# hydrogen_sensors_board_v2.net
KiCad netlist of a schematic drawn in EAGLE
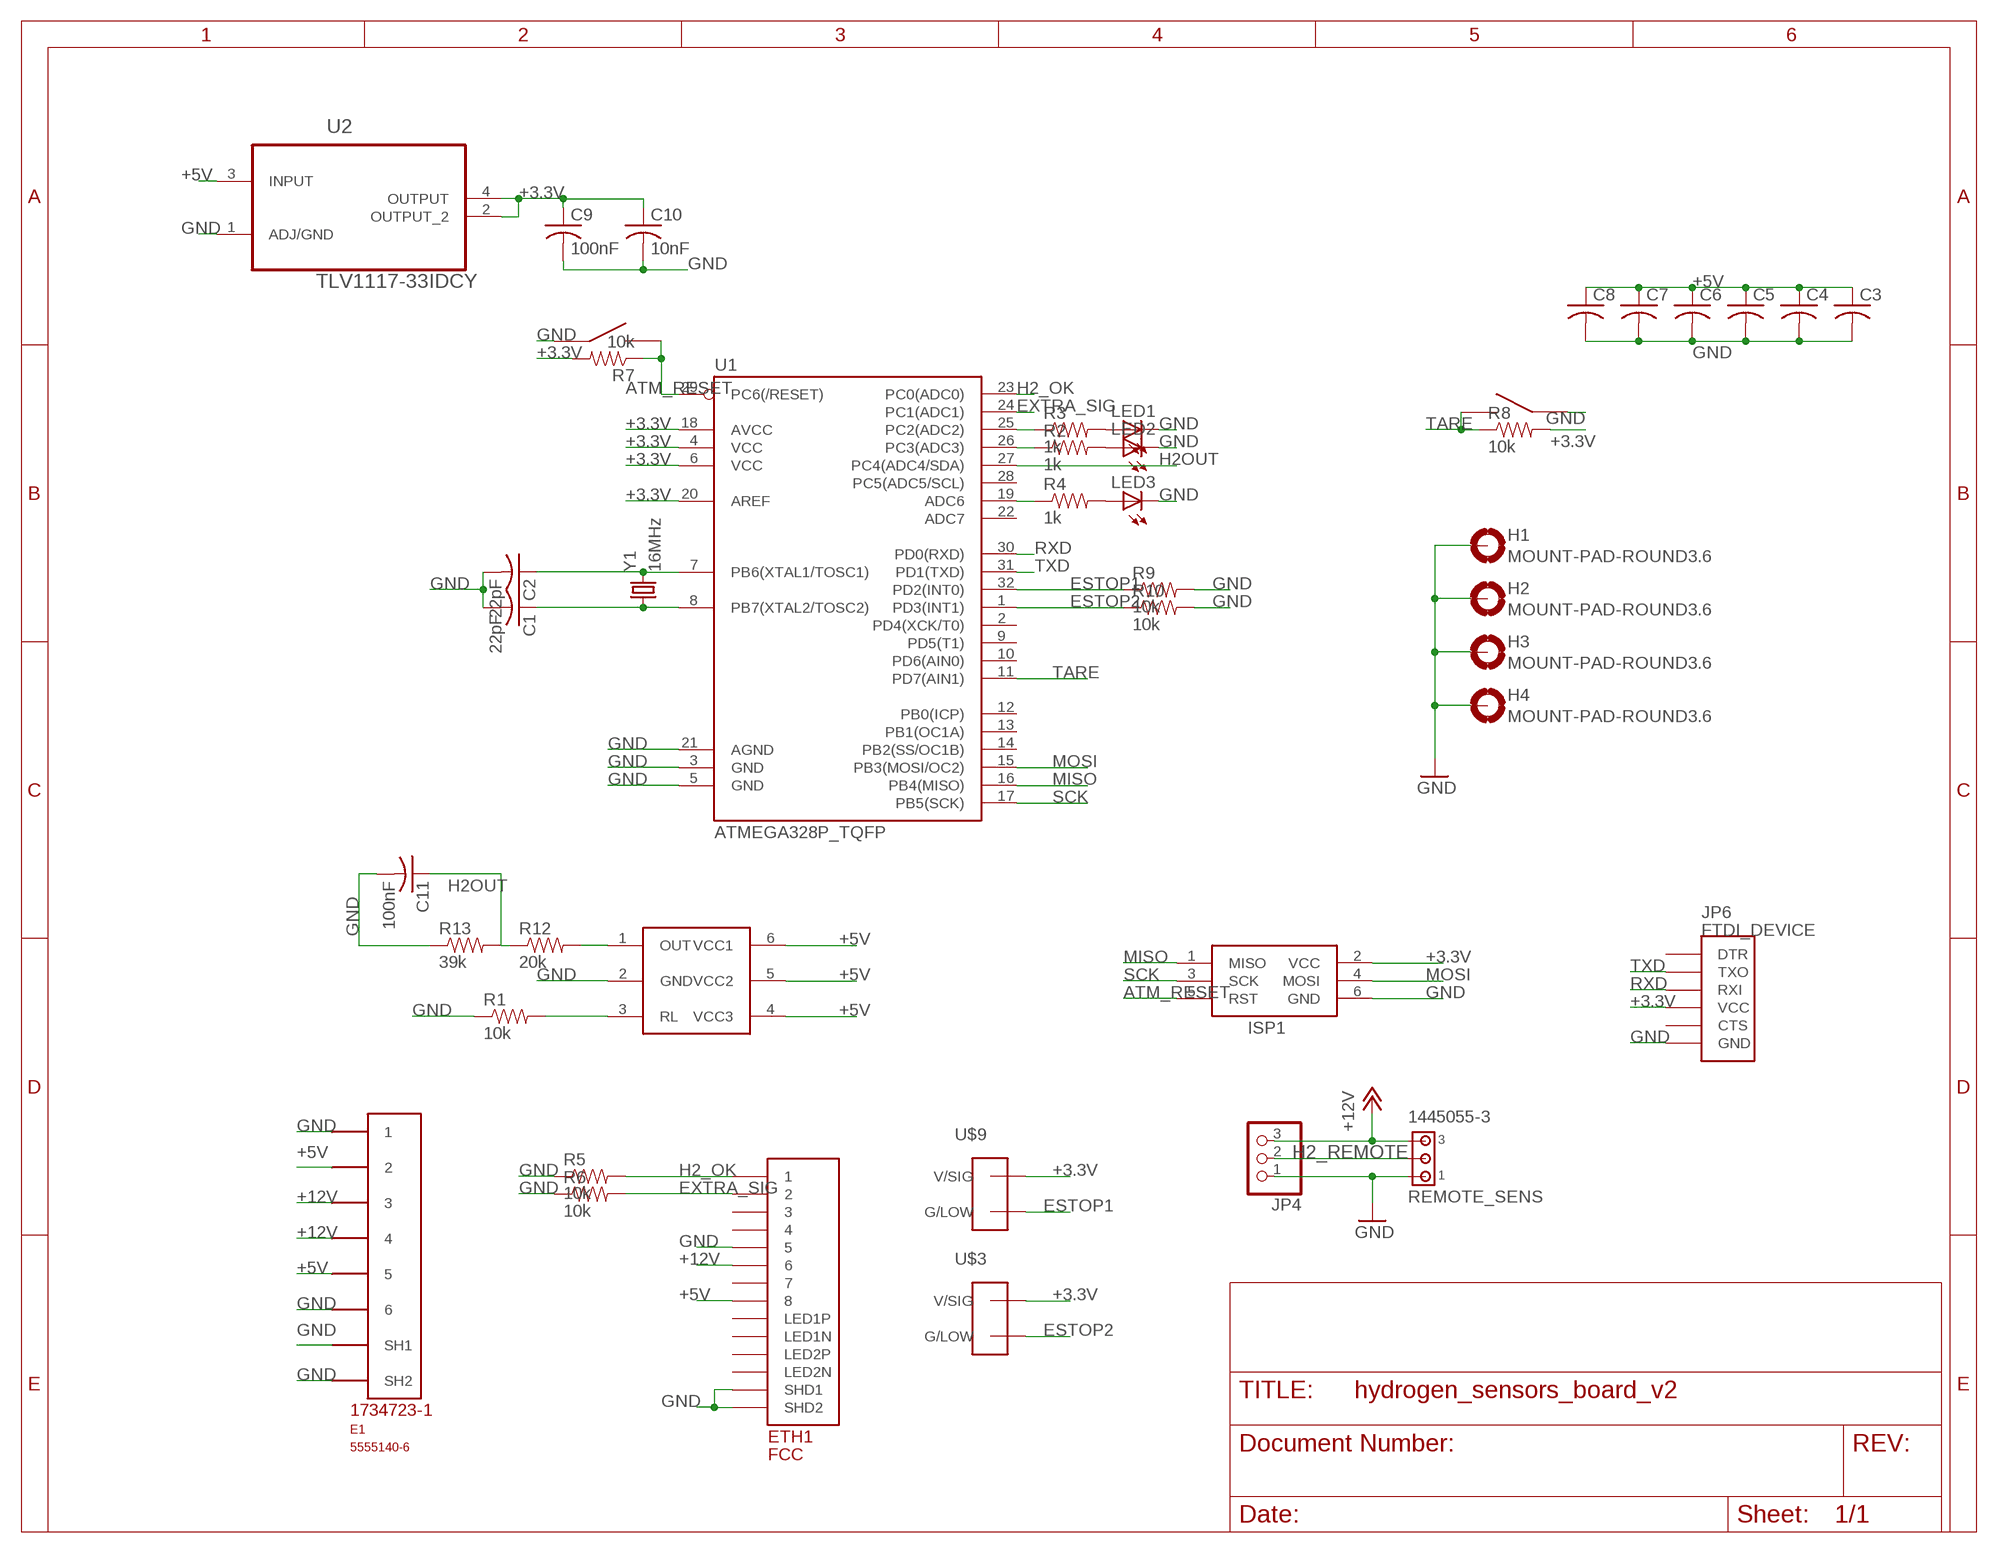
[diagram p0: schematic, sheet 1]

(export (version "E")
  (design (tool "Eeschema 10.0.6"))
  (components
    (comp (ref "C1")
      (value "22pF")
      (footprint "eagle-import:C0603K")
      (libsource (lib "eagle-import") (part "C-USC0603K"))
    )
    (comp (ref "C2")
      (value "22pF")
      (footprint "eagle-import:C0603K")
      (libsource (lib "eagle-import") (part "C-USC0603K"))
    )
    (comp (ref "C3")
      (value "C-USC0603")
      (footprint "eagle-import:C0603")
      (libsource (lib "eagle-import") (part "C-USC0603"))
    )
    (comp (ref "C4")
      (value "C-USC0603")
      (footprint "eagle-import:C0603")
      (libsource (lib "eagle-import") (part "C-USC0603"))
    )
    (comp (ref "C5")
      (value "C-USC0603")
      (footprint "eagle-import:C0603")
      (libsource (lib "eagle-import") (part "C-USC0603"))
    )
    (comp (ref "C6")
      (value "C-USC0603")
      (footprint "eagle-import:C0603")
      (libsource (lib "eagle-import") (part "C-USC0603"))
    )
    (comp (ref "C7")
      (value "C-USC0603")
      (footprint "eagle-import:C0603")
      (libsource (lib "eagle-import") (part "C-USC0603"))
    )
    (comp (ref "C8")
      (value "C-USC0603")
      (footprint "eagle-import:C0603")
      (libsource (lib "eagle-import") (part "C-USC0603"))
    )
    (comp (ref "C9")
      (value "100nF")
      (footprint "eagle-import:C0603")
      (libsource (lib "eagle-import") (part "C-USC0603"))
    )
    (comp (ref "C10")
      (value "10nF")
      (footprint "eagle-import:C0603")
      (libsource (lib "eagle-import") (part "C-USC0603"))
    )
    (comp (ref "C11")
      (value "100nF")
      (footprint "eagle-import:C0603")
      (libsource (lib "eagle-import") (part "C-USC0603"))
    )
    (comp (ref "E1")
      (value "5555140-6")
      (footprint "eagle-import:1734723-1_RJ11")
      (libsource (lib "eagle-import") (part "5555140-6"))
    )
    (comp (ref "ETH1")
      (value "FCC")
      (footprint "eagle-import:A122645-ND")
      (libsource (lib "eagle-import") (part "ETHERNET"))
    )
    (comp (ref "H1")
      (value "MOUNT-PAD-ROUND3.6")
      (footprint "eagle-import:3,6-PAD")
      (libsource (lib "eagle-import") (part "MOUNT-PAD-ROUND3.6"))
    )
    (comp (ref "H2")
      (value "MOUNT-PAD-ROUND3.6")
      (footprint "eagle-import:3,6-PAD")
      (libsource (lib "eagle-import") (part "MOUNT-PAD-ROUND3.6"))
    )
    (comp (ref "H3")
      (value "MOUNT-PAD-ROUND3.6")
      (footprint "eagle-import:3,6-PAD")
      (libsource (lib "eagle-import") (part "MOUNT-PAD-ROUND3.6"))
    )
    (comp (ref "H4")
      (value "MOUNT-PAD-ROUND3.6")
      (footprint "eagle-import:3,6-PAD")
      (libsource (lib "eagle-import") (part "MOUNT-PAD-ROUND3.6"))
    )
    (comp (ref "ISP1")
      (value "AVRISP-BOX")
      (footprint "eagle-import:AVRISP-BOX")
      (libsource (lib "eagle-import") (part "AVRISP-BOX"))
    )
    (comp (ref "JP4")
      (value "PINHD-1X3")
      (footprint "eagle-import:1X03")
      (libsource (lib "eagle-import") (part "PINHD-1X3"))
    )
    (comp (ref "JP6")
      (value "FTDI_DEVICE")
      (footprint "eagle-import:FTDI_DEVICE_SIDE")
      (libsource (lib "eagle-import") (part "FTDI_DEVICE"))
    )
    (comp (ref "LED1")
      (value "LEDCHIPLED_0805")
      (footprint "eagle-import:CHIPLED_0805")
      (libsource (lib "eagle-import") (part "LEDCHIPLED_0805"))
    )
    (comp (ref "LED2")
      (value "LEDCHIPLED_0805")
      (footprint "eagle-import:CHIPLED_0805")
      (libsource (lib "eagle-import") (part "LEDCHIPLED_0805"))
    )
    (comp (ref "LED3")
      (value "LEDCHIPLED_0805")
      (footprint "eagle-import:CHIPLED_0805")
      (libsource (lib "eagle-import") (part "LEDCHIPLED_0805"))
    )
    (comp (ref "R1")
      (value "10k")
      (footprint "eagle-import:0603-RES")
      (libsource (lib "eagle-import") (part "RESISTOR0603-RES"))
    )
    (comp (ref "R2")
      (value "1k")
      (footprint "eagle-import:0603-RES")
      (libsource (lib "eagle-import") (part "SparkFun-Resistors_RESISTOR0603-RES"))
    )
    (comp (ref "R3")
      (value "1k")
      (footprint "eagle-import:0603-RES")
      (libsource (lib "eagle-import") (part "SparkFun-Resistors_RESISTOR0603-RES"))
    )
    (comp (ref "R4")
      (value "1k")
      (footprint "eagle-import:0603-RES")
      (libsource (lib "eagle-import") (part "SparkFun-Resistors_RESISTOR0603-RES"))
    )
    (comp (ref "R5")
      (value "10k")
      (footprint "eagle-import:0603-RES")
      (libsource (lib "eagle-import") (part "RESISTOR0603-RES"))
    )
    (comp (ref "R6")
      (value "10k")
      (footprint "eagle-import:0603-RES")
      (libsource (lib "eagle-import") (part "RESISTOR0603-RES"))
    )
    (comp (ref "R7")
      (value "10k")
      (footprint "eagle-import:0603-RES")
      (libsource (lib "eagle-import") (part "SparkFun-Resistors_RESISTOR0603-RES"))
    )
    (comp (ref "R8")
      (value "10k")
      (footprint "eagle-import:0603-RES")
      (libsource (lib "eagle-import") (part "SparkFun-Resistors_RESISTOR0603-RES"))
    )
    (comp (ref "R9")
      (value "10k")
      (footprint "eagle-import:0603-RES")
      (libsource (lib "eagle-import") (part "RESISTOR0603-RES"))
    )
    (comp (ref "R10")
      (value "10k")
      (footprint "eagle-import:0603-RES")
      (libsource (lib "eagle-import") (part "RESISTOR0603-RES"))
    )
    (comp (ref "R12")
      (value "20k")
      (footprint "eagle-import:0603-RES")
      (libsource (lib "eagle-import") (part "RESISTOR0603-RES"))
    )
    (comp (ref "R13")
      (value "39k")
      (footprint "eagle-import:0603-RES")
      (libsource (lib "eagle-import") (part "RESISTOR0603-RES"))
    )
    (comp (ref "REMOTE_SENS")
      (value "1445055-3")
      (footprint "eagle-import:1445055-3")
      (libsource (lib "eagle-import") (part "1445055-3"))
    )
    (comp (ref "U$1")
      (value "MQ-8MQ-8")
      (footprint "eagle-import:MQ-8")
      (libsource (lib "eagle-import") (part "MQ-8MQ-8"))
    )
    (comp (ref "U$2")
      (value "EG4621CT-ND")
      (footprint "eagle-import:EG4621CT-ND")
      (libsource (lib "eagle-import") (part "EG4621CT-ND"))
    )
    (comp (ref "U$3")
      (value "TE770966")
      (footprint "eagle-import:2X1-MATE-N-LOCK")
      (libsource (lib "eagle-import") (part "TE770966"))
    )
    (comp (ref "U$9")
      (value "TE770966")
      (footprint "eagle-import:2X1-MATE-N-LOCK")
      (libsource (lib "eagle-import") (part "TE770966"))
    )
    (comp (ref "U$10")
      (value "EG4621CT-ND")
      (footprint "eagle-import:EG4621CT-ND")
      (libsource (lib "eagle-import") (part "EG4621CT-ND"))
    )
    (comp (ref "U1")
      (value "ATMEGA328P_TQFP")
      (footprint "eagle-import:TQFP32-08")
      (libsource (lib "eagle-import") (part "ATMEGA328P_TQFP"))
    )
    (comp (ref "U2")
      (value "TLV1117-33IDCY")
      (footprint "eagle-import:SOT230P700X180-4N")
      (libsource (lib "eagle-import") (part "TLV1117-33IDCY"))
    )
    (comp (ref "Y1")
      (value "16MHz")
      (footprint "eagle-import:HC49US")
      (libsource (lib "eagle-import") (part "CRYSTALHC49US"))
    )
  )
  (nets
    (net (code "1") (name "+12V") (class "Default")
      (node (ref "E1") (pin "3") (pinfunction "3_3") (pintype "bidirectional"))
      (node (ref "E1") (pin "4") (pinfunction "4_4") (pintype "bidirectional"))
      (node (ref "ETH1") (pin "P$6") (pinfunction "6_P$6") (pintype "bidirectional"))
      (node (ref "JP4") (pin "3") (pinfunction "3_3") (pintype "passive"))
      (node (ref "REMOTE_SENS") (pin "3") (pinfunction "3_3") (pintype "passive"))
    )
    (net (code "2") (name "/+3.3V") (class "Default")
      (node (ref "C10") (pin "1") (pinfunction "1_1") (pintype "passive"))
      (node (ref "C9") (pin "1") (pinfunction "1_1") (pintype "passive"))
      (node (ref "ISP1") (pin "2") (pinfunction "VCC_2") (pintype "power_in"))
      (node (ref "JP6") (pin "P$4") (pinfunction "VCC_P$4") (pintype "bidirectional"))
      (node (ref "R7") (pin "2") (pinfunction "2_2") (pintype "passive"))
      (node (ref "R8") (pin "2") (pinfunction "2_2") (pintype "passive"))
      (node (ref "U$3") (pin "CIRCUIT1") (pinfunction "V/SIG_CIRCUIT1") (pintype "bidirectional"))
      (node (ref "U$9") (pin "CIRCUIT1") (pinfunction "V/SIG_CIRCUIT1") (pintype "bidirectional"))
      (node (ref "U1") (pin "18") (pinfunction "AVCC_18") (pintype "bidirectional"))
      (node (ref "U1") (pin "20") (pinfunction "AREF_20") (pintype "bidirectional"))
      (node (ref "U1") (pin "4") (pinfunction "VCC_4") (pintype "bidirectional"))
      (node (ref "U1") (pin "6") (pinfunction "VCC_6") (pintype "bidirectional"))
      (node (ref "U2") (pin "2") (pinfunction "OUTPUT_2_2") (pintype "output"))
      (node (ref "U2") (pin "4") (pinfunction "OUTPUT_4") (pintype "output"))
    )
    (net (code "3") (name "/+5V") (class "Default")
      (node (ref "C3") (pin "1") (pinfunction "1_1") (pintype "passive"))
      (node (ref "C4") (pin "1") (pinfunction "1_1") (pintype "passive"))
      (node (ref "C5") (pin "1") (pinfunction "1_1") (pintype "passive"))
      (node (ref "C6") (pin "1") (pinfunction "1_1") (pintype "passive"))
      (node (ref "C7") (pin "1") (pinfunction "1_1") (pintype "passive"))
      (node (ref "C8") (pin "1") (pinfunction "1_1") (pintype "passive"))
      (node (ref "E1") (pin "2") (pinfunction "2_2") (pintype "bidirectional"))
      (node (ref "E1") (pin "5") (pinfunction "5_5") (pintype "bidirectional"))
      (node (ref "ETH1") (pin "P$8") (pinfunction "8_P$8") (pintype "bidirectional"))
      (node (ref "U$1") (pin "4") (pinfunction "VCC3_4") (pintype "bidirectional"))
      (node (ref "U$1") (pin "5") (pinfunction "VCC2_5") (pintype "bidirectional"))
      (node (ref "U$1") (pin "6") (pinfunction "VCC1_6") (pintype "bidirectional"))
      (node (ref "U2") (pin "3") (pinfunction "INPUT_3") (pintype "input"))
    )
    (net (code "4") (name "/ATM_RESET") (class "Default")
      (node (ref "ISP1") (pin "5") (pinfunction "RST_5") (pintype "output"))
      (node (ref "R7") (pin "1") (pinfunction "1_1") (pintype "passive"))
      (node (ref "U$10") (pin "P$3") (pinfunction "P$2_P$3") (pintype "bidirectional"))
      (node (ref "U$10") (pin "P$4") (pinfunction "P$2_P$4") (pintype "bidirectional"))
      (node (ref "U1") (pin "29") (pinfunction "PC6(/RESET)_29") (pintype "bidirectional"))
    )
    (net (code "5") (name "/ESTOP1") (class "Default")
      (node (ref "R9") (pin "1") (pinfunction "1_1") (pintype "passive"))
      (node (ref "U$9") (pin "CIRCUIT2") (pinfunction "G/LOW_CIRCUIT2") (pintype "bidirectional"))
      (node (ref "U1") (pin "32") (pinfunction "PD2(INT0)_32") (pintype "bidirectional"))
    )
    (net (code "6") (name "/ESTOP2") (class "Default")
      (node (ref "R10") (pin "1") (pinfunction "1_1") (pintype "passive"))
      (node (ref "U$3") (pin "CIRCUIT2") (pinfunction "G/LOW_CIRCUIT2") (pintype "bidirectional"))
      (node (ref "U1") (pin "1") (pinfunction "PD3(INT1)_1") (pintype "bidirectional"))
    )
    (net (code "7") (name "/EXTRA_SIG") (class "Default")
      (node (ref "ETH1") (pin "P$2") (pinfunction "2_P$2") (pintype "bidirectional"))
      (node (ref "R6") (pin "2") (pinfunction "2_2") (pintype "passive"))
      (node (ref "U1") (pin "24") (pinfunction "PC1(ADC1)_24") (pintype "bidirectional"))
    )
    (net (code "8") (name "/H2OUT") (class "Default")
      (node (ref "C11") (pin "1") (pinfunction "1_1") (pintype "passive"))
      (node (ref "R12") (pin "1") (pinfunction "1_1") (pintype "passive"))
      (node (ref "R13") (pin "2") (pinfunction "2_2") (pintype "passive"))
      (node (ref "U1") (pin "27") (pinfunction "PC4(ADC4/SDA)_27") (pintype "bidirectional"))
    )
    (net (code "9") (name "/H2_OK") (class "Default")
      (node (ref "ETH1") (pin "P$1") (pinfunction "1_P$1") (pintype "bidirectional"))
      (node (ref "R5") (pin "2") (pinfunction "2_2") (pintype "passive"))
      (node (ref "U1") (pin "23") (pinfunction "PC0(ADC0)_23") (pintype "bidirectional"))
    )
    (net (code "10") (name "/H2_REMOTE") (class "Default")
      (node (ref "JP4") (pin "2") (pinfunction "2_2") (pintype "passive"))
      (node (ref "REMOTE_SENS") (pin "2") (pinfunction "2_2") (pintype "passive"))
    )
    (net (code "11") (name "/MISO") (class "Default")
      (node (ref "ISP1") (pin "1") (pinfunction "MISO_1") (pintype "input"))
      (node (ref "U1") (pin "16") (pinfunction "PB4(MISO)_16") (pintype "bidirectional"))
    )
    (net (code "12") (name "/MOSI") (class "Default")
      (node (ref "ISP1") (pin "4") (pinfunction "MOSI_4") (pintype "output"))
      (node (ref "U1") (pin "15") (pinfunction "PB3(MOSI/OC2)_15") (pintype "bidirectional"))
    )
    (net (code "13") (name "/RXD") (class "Default")
      (node (ref "JP6") (pin "P$3") (pinfunction "RXI_P$3") (pintype "bidirectional"))
      (node (ref "U1") (pin "30") (pinfunction "PD0(RXD)_30") (pintype "bidirectional"))
    )
    (net (code "14") (name "/SCK") (class "Default")
      (node (ref "ISP1") (pin "3") (pinfunction "SCK_3") (pintype "output"))
      (node (ref "U1") (pin "17") (pinfunction "PB5(SCK)_17") (pintype "bidirectional"))
    )
    (net (code "15") (name "/TARE") (class "Default")
      (node (ref "R8") (pin "1") (pinfunction "1_1") (pintype "passive"))
      (node (ref "U$2") (pin "P$3") (pinfunction "P$2_P$3") (pintype "bidirectional"))
      (node (ref "U$2") (pin "P$4") (pinfunction "P$2_P$4") (pintype "bidirectional"))
      (node (ref "U1") (pin "11") (pinfunction "PD7(AIN1)_11") (pintype "bidirectional"))
    )
    (net (code "16") (name "/TXD") (class "Default")
      (node (ref "JP6") (pin "P$2") (pinfunction "TXO_P$2") (pintype "bidirectional"))
      (node (ref "U1") (pin "31") (pinfunction "PD1(TXD)_31") (pintype "bidirectional"))
    )
    (net (code "17") (name "GND") (class "Default")
      (node (ref "C1") (pin "2") (pinfunction "2_2") (pintype "passive"))
      (node (ref "C10") (pin "2") (pinfunction "2_2") (pintype "passive"))
      (node (ref "C11") (pin "2") (pinfunction "2_2") (pintype "passive"))
      (node (ref "C2") (pin "2") (pinfunction "2_2") (pintype "passive"))
      (node (ref "C3") (pin "2") (pinfunction "2_2") (pintype "passive"))
      (node (ref "C4") (pin "2") (pinfunction "2_2") (pintype "passive"))
      (node (ref "C5") (pin "2") (pinfunction "2_2") (pintype "passive"))
      (node (ref "C6") (pin "2") (pinfunction "2_2") (pintype "passive"))
      (node (ref "C7") (pin "2") (pinfunction "2_2") (pintype "passive"))
      (node (ref "C8") (pin "2") (pinfunction "2_2") (pintype "passive"))
      (node (ref "C9") (pin "2") (pinfunction "2_2") (pintype "passive"))
      (node (ref "E1") (pin "1") (pinfunction "1_1") (pintype "bidirectional"))
      (node (ref "E1") (pin "6") (pinfunction "6_6") (pintype "bidirectional"))
      (node (ref "E1") (pin "SH1") (pinfunction "SH1_SH1") (pintype "bidirectional"))
      (node (ref "E1") (pin "SH2") (pinfunction "SH2_SH2") (pintype "bidirectional"))
      (node (ref "ETH1") (pin "P$13") (pinfunction "SHD1_P$13") (pintype "bidirectional"))
      (node (ref "ETH1") (pin "P$14") (pinfunction "SHD2_P$14") (pintype "bidirectional"))
      (node (ref "ETH1") (pin "P$5") (pinfunction "5_P$5") (pintype "bidirectional"))
      (node (ref "H1") (pin "B3,6") (pinfunction "MOUNT_B3,6") (pintype "passive"))
      (node (ref "H2") (pin "B3,6") (pinfunction "MOUNT_B3,6") (pintype "passive"))
      (node (ref "H3") (pin "B3,6") (pinfunction "MOUNT_B3,6") (pintype "passive"))
      (node (ref "H4") (pin "B3,6") (pinfunction "MOUNT_B3,6") (pintype "passive"))
      (node (ref "ISP1") (pin "6") (pinfunction "GND_6") (pintype "power_in"))
      (node (ref "JP4") (pin "1") (pinfunction "1_1") (pintype "passive"))
      (node (ref "JP6") (pin "P$6") (pinfunction "GND_P$6") (pintype "bidirectional"))
      (node (ref "LED1") (pin "C") (pinfunction "C_C") (pintype "passive"))
      (node (ref "LED2") (pin "C") (pinfunction "C_C") (pintype "passive"))
      (node (ref "LED3") (pin "C") (pinfunction "C_C") (pintype "passive"))
      (node (ref "R1") (pin "1") (pinfunction "1_1") (pintype "passive"))
      (node (ref "R10") (pin "2") (pinfunction "2_2") (pintype "passive"))
      (node (ref "R13") (pin "1") (pinfunction "1_1") (pintype "passive"))
      (node (ref "R5") (pin "1") (pinfunction "1_1") (pintype "passive"))
      (node (ref "R6") (pin "1") (pinfunction "1_1") (pintype "passive"))
      (node (ref "R9") (pin "2") (pinfunction "2_2") (pintype "passive"))
      (node (ref "REMOTE_SENS") (pin "1") (pinfunction "1_1") (pintype "passive"))
      (node (ref "U$1") (pin "2") (pinfunction "GND_2") (pintype "bidirectional"))
      (node (ref "U$10") (pin "P$1") (pinfunction "P$1_P$1") (pintype "bidirectional"))
      (node (ref "U$10") (pin "P$2") (pinfunction "P$1_P$2") (pintype "bidirectional"))
      (node (ref "U$2") (pin "P$1") (pinfunction "P$1_P$1") (pintype "bidirectional"))
      (node (ref "U$2") (pin "P$2") (pinfunction "P$1_P$2") (pintype "bidirectional"))
      (node (ref "U1") (pin "21") (pinfunction "AGND_21") (pintype "bidirectional"))
      (node (ref "U1") (pin "3") (pinfunction "GND_3") (pintype "bidirectional"))
      (node (ref "U1") (pin "5") (pinfunction "GND_5") (pintype "bidirectional"))
      (node (ref "U2") (pin "1") (pinfunction "ADJ/GND_1") (pintype "input"))
    )
    (net (code "18") (name "Net-(LED1-PadA)") (class "Default")
      (node (ref "LED1") (pin "A") (pinfunction "A_A") (pintype "passive"))
      (node (ref "R3") (pin "2") (pinfunction "2_2") (pintype "passive"))
    )
    (net (code "19") (name "Net-(LED2-PadA)") (class "Default")
      (node (ref "LED2") (pin "A") (pinfunction "A_A") (pintype "passive"))
      (node (ref "R2") (pin "2") (pinfunction "2_2") (pintype "passive"))
    )
    (net (code "20") (name "Net-(LED3-PadA)") (class "Default")
      (node (ref "LED3") (pin "A") (pinfunction "A_A") (pintype "passive"))
      (node (ref "R4") (pin "2") (pinfunction "2_2") (pintype "passive"))
    )
    (net (code "21") (name "Net-(U$1-OUT)") (class "Default")
      (node (ref "R12") (pin "2") (pinfunction "2_2") (pintype "passive"))
      (node (ref "U$1") (pin "1") (pinfunction "OUT_1") (pintype "bidirectional"))
    )
    (net (code "22") (name "Net-(U$1-RL)") (class "Default")
      (node (ref "R1") (pin "2") (pinfunction "2_2") (pintype "passive"))
      (node (ref "U$1") (pin "3") (pinfunction "RL_3") (pintype "bidirectional"))
    )
    (net (code "23") (name "Net-(U1-ADC6)") (class "Default")
      (node (ref "R4") (pin "1") (pinfunction "1_1") (pintype "passive"))
      (node (ref "U1") (pin "19") (pinfunction "ADC6_19") (pintype "bidirectional"))
    )
    (net (code "24") (name "Net-(U1-PB6(XTAL1{slash}TOSC1))") (class "Default")
      (node (ref "C2") (pin "1") (pinfunction "1_1") (pintype "passive"))
      (node (ref "U1") (pin "7") (pinfunction "PB6(XTAL1/TOSC1)_7") (pintype "bidirectional"))
      (node (ref "Y1") (pin "2") (pinfunction "2_2") (pintype "passive"))
    )
    (net (code "25") (name "Net-(U1-PB7(XTAL2{slash}TOSC2))") (class "Default")
      (node (ref "C1") (pin "1") (pinfunction "1_1") (pintype "passive"))
      (node (ref "U1") (pin "8") (pinfunction "PB7(XTAL2/TOSC2)_8") (pintype "bidirectional"))
      (node (ref "Y1") (pin "1") (pinfunction "1_1") (pintype "passive"))
    )
    (net (code "26") (name "Net-(U1-PC2(ADC2))") (class "Default")
      (node (ref "R3") (pin "1") (pinfunction "1_1") (pintype "passive"))
      (node (ref "U1") (pin "25") (pinfunction "PC2(ADC2)_25") (pintype "bidirectional"))
    )
    (net (code "27") (name "Net-(U1-PC3(ADC3))") (class "Default")
      (node (ref "R2") (pin "1") (pinfunction "1_1") (pintype "passive"))
      (node (ref "U1") (pin "26") (pinfunction "PC3(ADC3)_26") (pintype "bidirectional"))
    )
    (net (code "28") (name "unconnected-(ETH1-3-PadP$3)") (class "Default")
      (node (ref "ETH1") (pin "P$3") (pinfunction "3_P$3") (pintype "bidirectional"))
    )
    (net (code "29") (name "unconnected-(ETH1-4-PadP$4)") (class "Default")
      (node (ref "ETH1") (pin "P$4") (pinfunction "4_P$4") (pintype "bidirectional"))
    )
    (net (code "30") (name "unconnected-(ETH1-7-PadP$7)") (class "Default")
      (node (ref "ETH1") (pin "P$7") (pinfunction "7_P$7") (pintype "bidirectional"))
    )
    (net (code "31") (name "unconnected-(ETH1-LED1N-PadP$9)") (class "Default")
      (node (ref "ETH1") (pin "P$9") (pinfunction "LED1N_P$9") (pintype "bidirectional"))
    )
    (net (code "32") (name "unconnected-(ETH1-LED1P-PadP$10)") (class "Default")
      (node (ref "ETH1") (pin "P$10") (pinfunction "LED1P_P$10") (pintype "bidirectional"))
    )
    (net (code "33") (name "unconnected-(ETH1-LED2N-PadP$11)") (class "Default")
      (node (ref "ETH1") (pin "P$11") (pinfunction "LED2N_P$11") (pintype "bidirectional"))
    )
    (net (code "34") (name "unconnected-(ETH1-LED2P-PadP$12)") (class "Default")
      (node (ref "ETH1") (pin "P$12") (pinfunction "LED2P_P$12") (pintype "bidirectional"))
    )
    (net (code "35") (name "unconnected-(JP6-CTS-PadP$5)") (class "Default")
      (node (ref "JP6") (pin "P$5") (pinfunction "CTS_P$5") (pintype "bidirectional"))
    )
    (net (code "36") (name "unconnected-(JP6-DTR-PadP$1)") (class "Default")
      (node (ref "JP6") (pin "P$1") (pinfunction "DTR_P$1") (pintype "bidirectional"))
    )
    (net (code "37") (name "unconnected-(U1-ADC7-Pad22)") (class "Default")
      (node (ref "U1") (pin "22") (pinfunction "ADC7_22") (pintype "bidirectional"))
    )
    (net (code "38") (name "unconnected-(U1-PB0(ICP)-Pad12)") (class "Default")
      (node (ref "U1") (pin "12") (pinfunction "PB0(ICP)_12") (pintype "bidirectional"))
    )
    (net (code "39") (name "unconnected-(U1-PB1(OC1A)-Pad13)") (class "Default")
      (node (ref "U1") (pin "13") (pinfunction "PB1(OC1A)_13") (pintype "bidirectional"))
    )
    (net (code "40") (name "unconnected-(U1-PB2(SS{slash}OC1B)-Pad14)") (class "Default")
      (node (ref "U1") (pin "14") (pinfunction "PB2(SS/OC1B)_14") (pintype "bidirectional"))
    )
    (net (code "41") (name "unconnected-(U1-PC5(ADC5{slash}SCL)-Pad28)") (class "Default")
      (node (ref "U1") (pin "28") (pinfunction "PC5(ADC5/SCL)_28") (pintype "bidirectional"))
    )
    (net (code "42") (name "unconnected-(U1-PD4(XCK{slash}T0)-Pad2)") (class "Default")
      (node (ref "U1") (pin "2") (pinfunction "PD4(XCK/T0)_2") (pintype "bidirectional"))
    )
    (net (code "43") (name "unconnected-(U1-PD5(T1)-Pad9)") (class "Default")
      (node (ref "U1") (pin "9") (pinfunction "PD5(T1)_9") (pintype "bidirectional"))
    )
    (net (code "44") (name "unconnected-(U1-PD6(AIN0)-Pad10)") (class "Default")
      (node (ref "U1") (pin "10") (pinfunction "PD6(AIN0)_10") (pintype "bidirectional"))
    )
  )
)
